# LED_CONTROLLER.net
KiCad netlist of a schematic drawn in Altium Designer
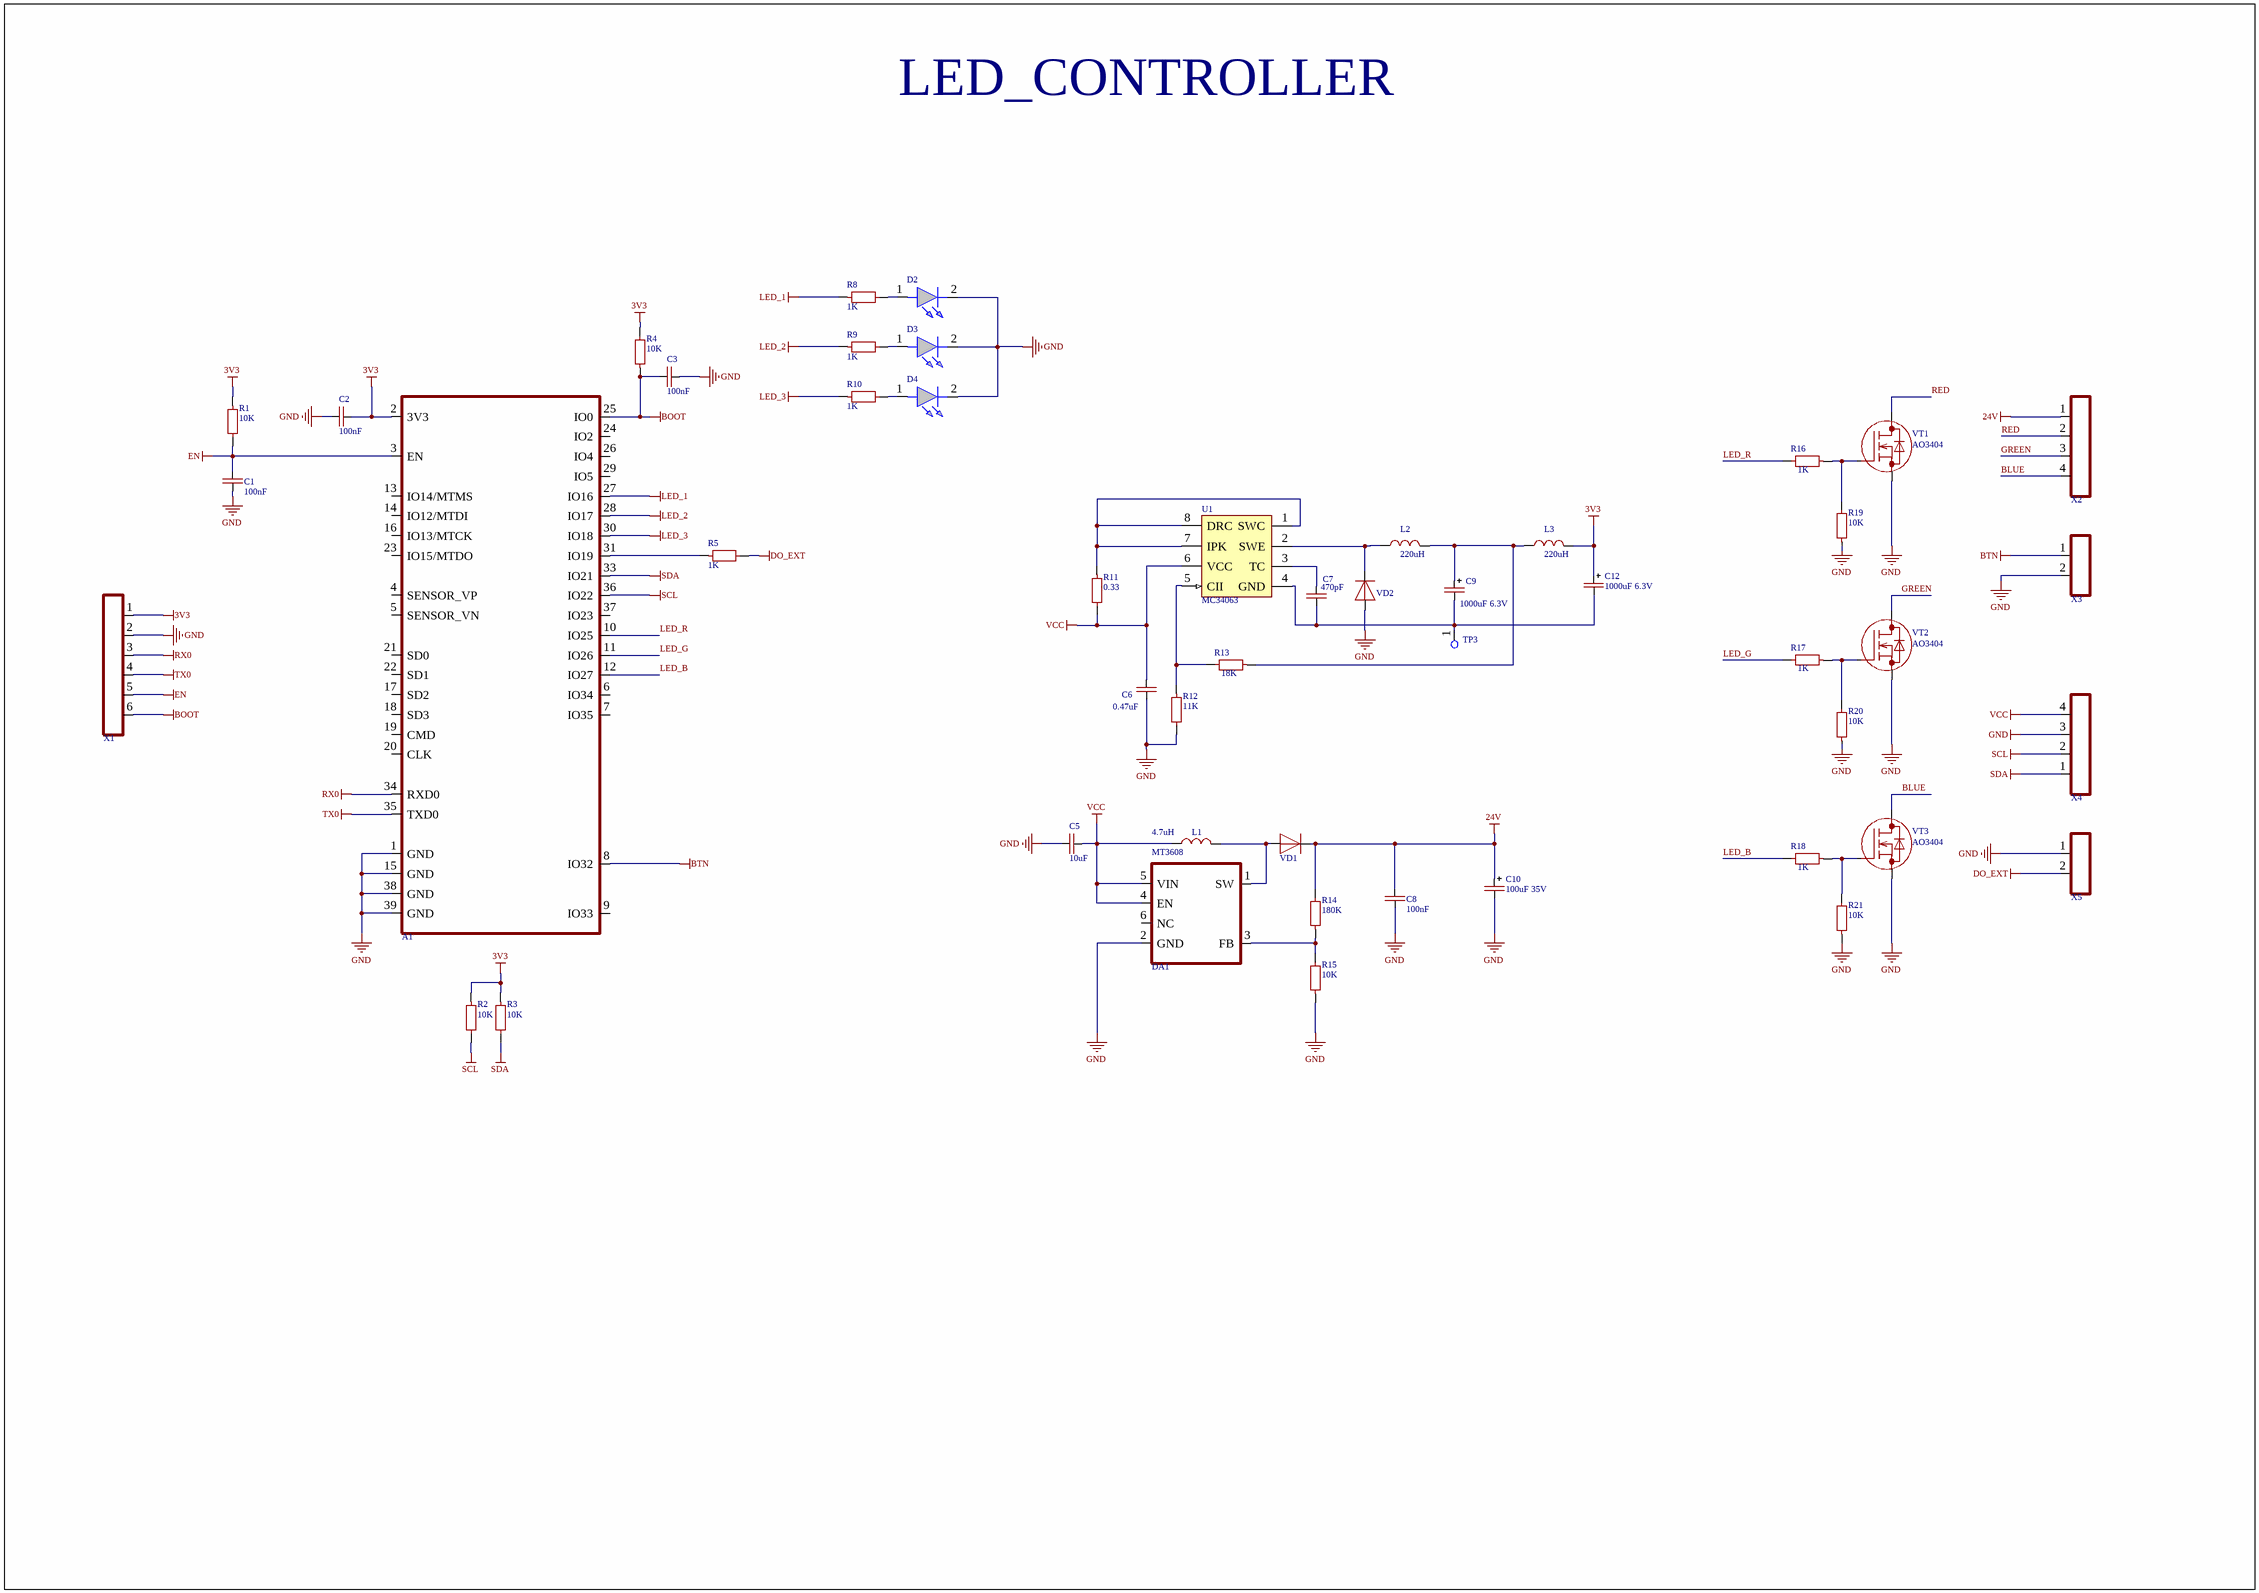
[diagram p0: LED_CONTROLLER.SchDoc]

(export (version "E")
  (design (tool "Eeschema 10.0.6"))
  (components
    (comp (ref "A1")
      (value "MOD-ESP32-WROOM-32E")
      (footprint "MOD-ESP32-WROOM-32E")
      (libsource (lib "MOD-ESP32-WROOM-32E") (part "MOD-ESP32-WROOM-32E"))
    )
    (comp (ref "C1")
      (value "100nF")
      (footprint "CAP-0805")
      (libsource (lib "PASSIVE_COMPONENTS") (part "CAP-NON-POLAR"))
    )
    (comp (ref "C2")
      (value "100nF")
      (footprint "CAP-0805")
      (libsource (lib "PASSIVE_COMPONENTS") (part "CAP-NON-POLAR"))
    )
    (comp (ref "C3")
      (value "100nF")
      (footprint "CAP-0805")
      (libsource (lib "PASSIVE_COMPONENTS") (part "CAP-NON-POLAR"))
    )
    (comp (ref "C5")
      (value "10uF")
      (footprint "CAP-1206")
      (libsource (lib "PASSIVE_COMPONENTS") (part "CAP-NON-POLAR"))
    )
    (comp (ref "C6")
      (value "0.47uF")
      (footprint "CAP-0805")
      (libsource (lib "PASSIVE_COMPONENTS") (part "CAP-NON-POLAR"))
    )
    (comp (ref "C7")
      (value "470pF")
      (footprint "CAP-0805")
      (libsource (lib "PASSIVE_COMPONENTS") (part "CAP-NON-POLAR"))
    )
    (comp (ref "C8")
      (value "100nF")
      (footprint "CAP-0805")
      (libsource (lib "PASSIVE_COMPONENTS") (part "CAP-NON-POLAR"))
    )
    (comp (ref "C9")
      (value "1000uF 6.3V")
      (footprint "CAPPOL_SMD_SIZE_E")
      (libsource (lib "PAS_COMPONENTS") (part "CAP-POLAR"))
    )
    (comp (ref "C10")
      (value "100uF 35V")
      (footprint "CAPPOL_SMD_SIZE_E")
      (libsource (lib "PAS_COMPONENTS") (part "CAP-POLAR"))
    )
    (comp (ref "C12")
      (value "1000uF 6.3V")
      (footprint "CAPPOL_SMD_SIZE_E")
      (libsource (lib "PAS_COMPONENTS") (part "CAP-POLAR"))
    )
    (comp (ref "D2")
      (value "151031YS06000")
      (footprint "LED_BLUE")
      (description "WURTH ELEKTRONIK - 151031YS06000 - LED, Yellow, Through Hole, T-1 (3mm), 30 mA, 2 V, 590 nm")
      (fields (field (name "MOUSER PART NUMBER") "710-151031YS06000"))
      (libsource (lib "Optic-LED") (part "LED"))
    )
    (comp (ref "D3")
      (value "151031YS06000")
      (footprint "LED_BLUE")
      (description "WURTH ELEKTRONIK - 151031YS06000 - LED, Yellow, Through Hole, T-1 (3mm), 30 mA, 2 V, 590 nm")
      (fields (field (name "MOUSER PART NUMBER") "710-151031YS06000"))
      (libsource (lib "Optic-LED") (part "LED"))
    )
    (comp (ref "D4")
      (value "151031YS06000")
      (footprint "LED_BLUE")
      (description "WURTH ELEKTRONIK - 151031YS06000 - LED, Yellow, Through Hole, T-1 (3mm), 30 mA, 2 V, 590 nm")
      (fields (field (name "MOUSER PART NUMBER") "710-151031YS06000"))
      (libsource (lib "Optic-LED") (part "LED"))
    )
    (comp (ref "DA1") (value "MT3608") (footprint "SOT23-6") (libsource (lib "MT3608") (part "MT3608")))
    (comp (ref "L1")
      (value "4.7uH")
      (footprint "IND-7850")
      (libsource (lib "PAS_COMPONENTS") (part "IND-CONST"))
    )
    (comp (ref "L2")
      (value "220uH")
      (footprint "IND-7850")
      (libsource (lib "PAS_COMPONENTS") (part "IND-CONST"))
    )
    (comp (ref "L3")
      (value "220uH")
      (footprint "IND-7850")
      (libsource (lib "PAS_COMPONENTS") (part "IND-CONST"))
    )
    (comp (ref "R1")
      (value "10K")
      (footprint "RES-0805")
      (libsource (lib "PAS_COMPONENTS") (part "RES-CONST"))
    )
    (comp (ref "R2")
      (value "10K")
      (footprint "RES-0805")
      (libsource (lib "PAS_COMPONENTS") (part "RES-CONST"))
    )
    (comp (ref "R3")
      (value "10K")
      (footprint "RES-0805")
      (libsource (lib "PAS_COMPONENTS") (part "RES-CONST"))
    )
    (comp (ref "R4")
      (value "10K")
      (footprint "RES-0805")
      (libsource (lib "PAS_COMPONENTS") (part "RES-CONST"))
    )
    (comp (ref "R5")
      (value "1K")
      (footprint "RES-0805")
      (libsource (lib "PAS_COMPONENTS") (part "RES-CONST"))
    )
    (comp (ref "R8")
      (value "1K")
      (footprint "RES-0805")
      (libsource (lib "PAS_COMPONENTS") (part "RES-CONST"))
    )
    (comp (ref "R9")
      (value "1K")
      (footprint "RES-0805")
      (libsource (lib "PAS_COMPONENTS") (part "RES-CONST"))
    )
    (comp (ref "R10")
      (value "1K")
      (footprint "RES-0805")
      (libsource (lib "PAS_COMPONENTS") (part "RES-CONST"))
    )
    (comp (ref "R11")
      (value "0.33")
      (footprint "RES-2512")
      (libsource (lib "PAS_COMPONENTS") (part "RES-CONST"))
    )
    (comp (ref "R12")
      (value "11K")
      (footprint "RES-0805")
      (libsource (lib "PAS_COMPONENTS") (part "RES-CONST"))
    )
    (comp (ref "R13")
      (value "18K")
      (footprint "RES-0805")
      (libsource (lib "PAS_COMPONENTS") (part "RES-CONST"))
    )
    (comp (ref "R14")
      (value "180K")
      (footprint "RES-0805")
      (libsource (lib "PAS_COMPONENTS") (part "RES-CONST"))
    )
    (comp (ref "R15")
      (value "10K")
      (footprint "RES-0805")
      (libsource (lib "PAS_COMPONENTS") (part "RES-CONST"))
    )
    (comp (ref "R16")
      (value "1K")
      (footprint "RES-0805")
      (libsource (lib "PAS_COMPONENTS") (part "RES-CONST"))
    )
    (comp (ref "R17")
      (value "1K")
      (footprint "RES-0805")
      (libsource (lib "PAS_COMPONENTS") (part "RES-CONST"))
    )
    (comp (ref "R18")
      (value "1K")
      (footprint "RES-0805")
      (libsource (lib "PAS_COMPONENTS") (part "RES-CONST"))
    )
    (comp (ref "R19")
      (value "10K")
      (footprint "RES-0805")
      (libsource (lib "PAS_COMPONENTS") (part "RES-CONST"))
    )
    (comp (ref "R20")
      (value "10K")
      (footprint "RES-0805")
      (libsource (lib "PAS_COMPONENTS") (part "RES-CONST"))
    )
    (comp (ref "R21")
      (value "10K")
      (footprint "RES-0805")
      (libsource (lib "PAS_COMPONENTS") (part "RES-CONST"))
    )
    (comp (ref "TP3")
      (value "Test_Point_PCB")
      (footprint "Pin_Test_Point(Orange)")
      (description "Test_Point")
      (libsource (lib "Connectors") (part "TP_PCB?"))
    )
    (comp (ref "U1")
      (value "MC34063")
      (footprint "SOIC-8_M")
      (libsource (lib "Integrated_Circuts") (part "MC34063"))
    )
    (comp (ref "VD1") (value "DIODE") (footprint "DO-214AC, SMA") (libsource (lib "DO214") (part "DIODE")))
    (comp (ref "VD2") (value "DIODE") (footprint "DO-214AC, SMA") (libsource (lib "DIODES") (part "DIODE")))
    (comp (ref "VT1")
      (value "AO3404")
      (footprint "SOT23-3")
      (libsource (lib "TRANSISTORS") (part "MOSFET-N-GDS"))
    )
    (comp (ref "VT2")
      (value "AO3404")
      (footprint "SOT23-3")
      (libsource (lib "TRANSISTORS") (part "MOSFET-N-GDS"))
    )
    (comp (ref "VT3")
      (value "AO3404")
      (footprint "SOT23-3")
      (libsource (lib "TRANSISTORS") (part "MOSFET-N-GDS"))
    )
    (comp (ref "X1")
      (value "CONN-6-PIN")
      (footprint "CONN-PLS-6-2.00mm")
      (libsource (lib "CONN_PLS") (part "CONN-6-PIN"))
    )
    (comp (ref "X2")
      (value "CONN-4-PIN")
      (footprint "CONN-PLS-4-2.54mm")
      (libsource (lib "XH 4PIN") (part "CONN-4-PIN"))
    )
    (comp (ref "X3") (value "CONN-2-PIN") (footprint "XH2") (libsource (lib "XH 2PIN") (part "CONN-2-PIN")))
    (comp (ref "X4")
      (value "CONN-4-PIN")
      (footprint "CONN-PLS-4-2.54mm")
      (libsource (lib "") (part "CONN-4-PIN_1"))
    )
    (comp (ref "X5") (value "CONN-2-PIN") (footprint "XH2") (libsource (lib "XH 2PIN") (part "CONN-2-PIN")))
  )
  (nets
    (net (code "1") (name "/BLUE") (class "Default")
      (node (ref "VT3") (pin "3") (pinfunction "D_3") (pintype "passive"))
      (node (ref "X2") (pin "4") (pinfunction "4_4") (pintype "passive"))
    )
    (net (code "2") (name "/GREEN") (class "Default")
      (node (ref "VT2") (pin "3") (pinfunction "D_3") (pintype "passive"))
      (node (ref "X2") (pin "3") (pinfunction "3_3") (pintype "passive"))
    )
    (net (code "3") (name "/LED_B") (class "Default")
      (node (ref "A1") (pin "12") (pinfunction "IO27_12") (pintype "passive"))
      (node (ref "R18") (pin "2") (pinfunction "2_2") (pintype "passive"))
    )
    (net (code "4") (name "/LED_G") (class "Default")
      (node (ref "A1") (pin "11") (pinfunction "IO26_11") (pintype "passive"))
      (node (ref "R17") (pin "2") (pinfunction "2_2") (pintype "passive"))
    )
    (net (code "5") (name "/LED_R") (class "Default")
      (node (ref "A1") (pin "10") (pinfunction "IO25_10") (pintype "passive"))
      (node (ref "R16") (pin "2") (pinfunction "2_2") (pintype "passive"))
    )
    (net (code "6") (name "/RED") (class "Default")
      (node (ref "VT1") (pin "3") (pinfunction "D_3") (pintype "passive"))
      (node (ref "X2") (pin "2") (pinfunction "2_2") (pintype "passive"))
    )
    (net (code "7") (name "3V3") (class "Default")
      (node (ref "A1") (pin "2") (pinfunction "3V3_2") (pintype "passive"))
      (node (ref "C12") (pin "1") (pinfunction "+_1") (pintype "passive"))
      (node (ref "C2") (pin "1") (pinfunction "1_1") (pintype "passive"))
      (node (ref "L3") (pin "2") (pinfunction "2_2") (pintype "passive"))
      (node (ref "R1") (pin "1") (pinfunction "1_1") (pintype "passive"))
      (node (ref "R2") (pin "1") (pinfunction "1_1") (pintype "passive"))
      (node (ref "R3") (pin "1") (pinfunction "1_1") (pintype "passive"))
      (node (ref "R4") (pin "2") (pinfunction "2_2") (pintype "passive"))
      (node (ref "X1") (pin "1") (pinfunction "1_1") (pintype "passive"))
    )
    (net (code "8") (name "24V") (class "Default")
      (node (ref "C10") (pin "1") (pinfunction "+_1") (pintype "passive"))
      (node (ref "C8") (pin "1") (pinfunction "1_1") (pintype "passive"))
      (node (ref "R14") (pin "2") (pinfunction "2_2") (pintype "passive"))
      (node (ref "VD1") (pin "1") (pinfunction "C_1") (pintype "passive"))
      (node (ref "X2") (pin "1") (pinfunction "1_1") (pintype "passive"))
    )
    (net (code "9") (name "BOOT") (class "Default")
      (node (ref "A1") (pin "25") (pinfunction "IO0_25") (pintype "passive"))
      (node (ref "C3") (pin "2") (pinfunction "2_2") (pintype "passive"))
      (node (ref "R4") (pin "1") (pinfunction "1_1") (pintype "passive"))
      (node (ref "X1") (pin "6") (pinfunction "6_6") (pintype "passive"))
    )
    (net (code "10") (name "BTN") (class "Default")
      (node (ref "A1") (pin "8") (pinfunction "IO32_8") (pintype "passive"))
      (node (ref "X3") (pin "1") (pinfunction "1_1") (pintype "passive"))
    )
    (net (code "11") (name "DO_EXT") (class "Default")
      (node (ref "R5") (pin "2") (pinfunction "2_2") (pintype "passive"))
      (node (ref "X5") (pin "2") (pinfunction "2_2") (pintype "passive"))
    )
    (net (code "12") (name "EN") (class "Default")
      (node (ref "A1") (pin "3") (pinfunction "EN_3") (pintype "passive"))
      (node (ref "C1") (pin "1") (pinfunction "1_1") (pintype "passive"))
      (node (ref "R1") (pin "2") (pinfunction "2_2") (pintype "passive"))
      (node (ref "X1") (pin "5") (pinfunction "5_5") (pintype "passive"))
    )
    (net (code "13") (name "GND") (class "Default")
      (node (ref "A1") (pin "1") (pinfunction "GND_1") (pintype "passive"))
      (node (ref "A1") (pin "15") (pinfunction "GND_15") (pintype "passive"))
      (node (ref "A1") (pin "38") (pinfunction "GND_38") (pintype "passive"))
      (node (ref "A1") (pin "39") (pinfunction "GND_39") (pintype "passive"))
      (node (ref "C1") (pin "2") (pinfunction "2_2") (pintype "passive"))
      (node (ref "C10") (pin "2") (pinfunction "-_2") (pintype "passive"))
      (node (ref "C2") (pin "2") (pinfunction "2_2") (pintype "passive"))
      (node (ref "C3") (pin "1") (pinfunction "1_1") (pintype "passive"))
      (node (ref "C5") (pin "2") (pinfunction "2_2") (pintype "passive"))
      (node (ref "C6") (pin "2") (pinfunction "2_2") (pintype "passive"))
      (node (ref "C8") (pin "2") (pinfunction "2_2") (pintype "passive"))
      (node (ref "D2") (pin "2") (pinfunction "K_2") (pintype "passive"))
      (node (ref "D3") (pin "2") (pinfunction "K_2") (pintype "passive"))
      (node (ref "D4") (pin "2") (pinfunction "K_2") (pintype "passive"))
      (node (ref "DA1") (pin "2") (pinfunction "GND_2") (pintype "passive"))
      (node (ref "R12") (pin "2") (pinfunction "2_2") (pintype "passive"))
      (node (ref "R15") (pin "1") (pinfunction "1_1") (pintype "passive"))
      (node (ref "R19") (pin "1") (pinfunction "1_1") (pintype "passive"))
      (node (ref "R20") (pin "1") (pinfunction "1_1") (pintype "passive"))
      (node (ref "R21") (pin "1") (pinfunction "1_1") (pintype "passive"))
      (node (ref "VD2") (pin "2") (pinfunction "A_2") (pintype "passive"))
      (node (ref "VT1") (pin "2") (pinfunction "S_2") (pintype "passive"))
      (node (ref "VT2") (pin "2") (pinfunction "S_2") (pintype "passive"))
      (node (ref "VT3") (pin "2") (pinfunction "S_2") (pintype "passive"))
      (node (ref "X1") (pin "2") (pinfunction "2_2") (pintype "passive"))
      (node (ref "X3") (pin "2") (pinfunction "2_2") (pintype "passive"))
      (node (ref "X4") (pin "3") (pinfunction "3_3") (pintype "passive"))
      (node (ref "X5") (pin "1") (pinfunction "1_1") (pintype "passive"))
    )
    (net (code "14") (name "LED_1") (class "Default")
      (node (ref "A1") (pin "27") (pinfunction "IO16_27") (pintype "passive"))
      (node (ref "R8") (pin "1") (pinfunction "1_1") (pintype "passive"))
    )
    (net (code "15") (name "LED_2") (class "Default")
      (node (ref "A1") (pin "28") (pinfunction "IO17_28") (pintype "passive"))
      (node (ref "R9") (pin "1") (pinfunction "1_1") (pintype "passive"))
    )
    (net (code "16") (name "LED_3") (class "Default")
      (node (ref "A1") (pin "30") (pinfunction "IO18_30") (pintype "passive"))
      (node (ref "R10") (pin "1") (pinfunction "1_1") (pintype "passive"))
    )
    (net (code "17") (name "Net-(A1-IO19)") (class "Default")
      (node (ref "A1") (pin "31") (pinfunction "IO19_31") (pintype "passive"))
      (node (ref "R5") (pin "1") (pinfunction "1_1") (pintype "passive"))
    )
    (net (code "18") (name "Net-(C9-+)") (class "Default")
      (node (ref "C9") (pin "1") (pinfunction "+_1") (pintype "passive"))
      (node (ref "L2") (pin "2") (pinfunction "2_2") (pintype "passive"))
      (node (ref "L3") (pin "1") (pinfunction "1_1") (pintype "passive"))
      (node (ref "R13") (pin "1") (pinfunction "1_1") (pintype "passive"))
    )
    (net (code "19") (name "Net-(C12--)") (class "Default")
      (node (ref "C12") (pin "2") (pinfunction "-_2") (pintype "passive"))
      (node (ref "C7") (pin "2") (pinfunction "2_2") (pintype "passive"))
      (node (ref "C9") (pin "2") (pinfunction "-_2") (pintype "passive"))
      (node (ref "TP3") (pin "1") (pinfunction "G9_1") (pintype "passive"))
      (node (ref "U1") (pin "4") (pinfunction "GND_4") (pintype "power_in"))
    )
    (net (code "20") (name "Net-(D2-A)") (class "Default")
      (node (ref "D2") (pin "1") (pinfunction "A_1") (pintype "passive"))
      (node (ref "R8") (pin "2") (pinfunction "2_2") (pintype "passive"))
    )
    (net (code "21") (name "Net-(D3-A)") (class "Default")
      (node (ref "D3") (pin "1") (pinfunction "A_1") (pintype "passive"))
      (node (ref "R9") (pin "2") (pinfunction "2_2") (pintype "passive"))
    )
    (net (code "22") (name "Net-(D4-A)") (class "Default")
      (node (ref "D4") (pin "1") (pinfunction "A_1") (pintype "passive"))
      (node (ref "R10") (pin "2") (pinfunction "2_2") (pintype "passive"))
    )
    (net (code "23") (name "Net-(DA1-FB)") (class "Default")
      (node (ref "DA1") (pin "3") (pinfunction "FB_3") (pintype "passive"))
      (node (ref "R14") (pin "1") (pinfunction "1_1") (pintype "passive"))
      (node (ref "R15") (pin "2") (pinfunction "2_2") (pintype "passive"))
    )
    (net (code "24") (name "Net-(DA1-SW)") (class "Default")
      (node (ref "DA1") (pin "1") (pinfunction "SW_1") (pintype "passive"))
      (node (ref "L1") (pin "2") (pinfunction "2_2") (pintype "passive"))
      (node (ref "VD1") (pin "2") (pinfunction "A_2") (pintype "passive"))
    )
    (net (code "25") (name "Net-(U1-CII)") (class "Default")
      (node (ref "R12") (pin "1") (pinfunction "1_1") (pintype "passive"))
      (node (ref "R13") (pin "2") (pinfunction "2_2") (pintype "passive"))
      (node (ref "U1") (pin "5") (pinfunction "CII_5") (pintype "input"))
    )
    (net (code "26") (name "Net-(U1-DRC)") (class "Default")
      (node (ref "R11") (pin "1") (pinfunction "1_1") (pintype "passive"))
      (node (ref "U1") (pin "1") (pinfunction "SWC_1") (pintype "open_collector"))
      (node (ref "U1") (pin "7") (pinfunction "IPK_7") (pintype "passive"))
      (node (ref "U1") (pin "8") (pinfunction "DRC_8") (pintype "open_collector"))
    )
    (net (code "27") (name "Net-(U1-SWE)") (class "Default")
      (node (ref "L2") (pin "1") (pinfunction "1_1") (pintype "passive"))
      (node (ref "U1") (pin "2") (pinfunction "SWE_2") (pintype "open_emitter"))
      (node (ref "VD2") (pin "1") (pinfunction "C_1") (pintype "passive"))
    )
    (net (code "28") (name "Net-(U1-TC)") (class "Default")
      (node (ref "C7") (pin "1") (pinfunction "1_1") (pintype "passive"))
      (node (ref "U1") (pin "3") (pinfunction "TC_3") (pintype "passive"))
    )
    (net (code "29") (name "Net-(VT1-G)") (class "Default")
      (node (ref "R16") (pin "1") (pinfunction "1_1") (pintype "passive"))
      (node (ref "R19") (pin "2") (pinfunction "2_2") (pintype "passive"))
      (node (ref "VT1") (pin "1") (pinfunction "G_1") (pintype "passive"))
    )
    (net (code "30") (name "Net-(VT2-G)") (class "Default")
      (node (ref "R17") (pin "1") (pinfunction "1_1") (pintype "passive"))
      (node (ref "R20") (pin "2") (pinfunction "2_2") (pintype "passive"))
      (node (ref "VT2") (pin "1") (pinfunction "G_1") (pintype "passive"))
    )
    (net (code "31") (name "Net-(VT3-G)") (class "Default")
      (node (ref "R18") (pin "1") (pinfunction "1_1") (pintype "passive"))
      (node (ref "R21") (pin "2") (pinfunction "2_2") (pintype "passive"))
      (node (ref "VT3") (pin "1") (pinfunction "G_1") (pintype "passive"))
    )
    (net (code "32") (name "RX0") (class "Default")
      (node (ref "A1") (pin "34") (pinfunction "RXD0_34") (pintype "passive"))
      (node (ref "X1") (pin "3") (pinfunction "3_3") (pintype "passive"))
    )
    (net (code "33") (name "SCL") (class "Default")
      (node (ref "A1") (pin "36") (pinfunction "IO22_36") (pintype "passive"))
      (node (ref "R2") (pin "2") (pinfunction "2_2") (pintype "passive"))
      (node (ref "X4") (pin "2") (pinfunction "2_2") (pintype "passive"))
    )
    (net (code "34") (name "SDA") (class "Default")
      (node (ref "A1") (pin "33") (pinfunction "IO21_33") (pintype "passive"))
      (node (ref "R3") (pin "2") (pinfunction "2_2") (pintype "passive"))
      (node (ref "X4") (pin "1") (pinfunction "1_1") (pintype "passive"))
    )
    (net (code "35") (name "TX0") (class "Default")
      (node (ref "A1") (pin "35") (pinfunction "TXD0_35") (pintype "passive"))
      (node (ref "X1") (pin "4") (pinfunction "4_4") (pintype "passive"))
    )
    (net (code "36") (name "VCC") (class "Default")
      (node (ref "C5") (pin "1") (pinfunction "1_1") (pintype "passive"))
      (node (ref "C6") (pin "1") (pinfunction "1_1") (pintype "passive"))
      (node (ref "DA1") (pin "4") (pinfunction "EN_4") (pintype "passive"))
      (node (ref "DA1") (pin "5") (pinfunction "VIN_5") (pintype "passive"))
      (node (ref "L1") (pin "1") (pinfunction "1_1") (pintype "passive"))
      (node (ref "R11") (pin "2") (pinfunction "2_2") (pintype "passive"))
      (node (ref "U1") (pin "6") (pinfunction "VCC_6") (pintype "power_in"))
      (node (ref "X4") (pin "4") (pinfunction "4_4") (pintype "passive"))
    )
    (net (code "37") (name "unconnected-(A1-CLK-Pad20)") (class "Default")
      (node (ref "A1") (pin "20") (pinfunction "CLK_20") (pintype "passive"))
    )
    (net (code "38") (name "unconnected-(A1-CMD-Pad19)") (class "Default")
      (node (ref "A1") (pin "19") (pinfunction "CMD_19") (pintype "passive"))
    )
    (net (code "39") (name "unconnected-(A1-IO2-Pad24)") (class "Default")
      (node (ref "A1") (pin "24") (pinfunction "IO2_24") (pintype "passive"))
    )
    (net (code "40") (name "unconnected-(A1-IO4-Pad26)") (class "Default")
      (node (ref "A1") (pin "26") (pinfunction "IO4_26") (pintype "passive"))
    )
    (net (code "41") (name "unconnected-(A1-IO5-Pad29)") (class "Default")
      (node (ref "A1") (pin "29") (pinfunction "IO5_29") (pintype "passive"))
    )
    (net (code "42") (name "unconnected-(A1-IO12{slash}MTDI-Pad14)") (class "Default")
      (node (ref "A1") (pin "14") (pinfunction "IO12/MTDI_14") (pintype "passive"))
    )
    (net (code "43") (name "unconnected-(A1-IO13{slash}MTCK-Pad16)") (class "Default")
      (node (ref "A1") (pin "16") (pinfunction "IO13/MTCK_16") (pintype "passive"))
    )
    (net (code "44") (name "unconnected-(A1-IO14{slash}MTMS-Pad13)") (class "Default")
      (node (ref "A1") (pin "13") (pinfunction "IO14/MTMS_13") (pintype "passive"))
    )
    (net (code "45") (name "unconnected-(A1-IO15{slash}MTDO-Pad23)") (class "Default")
      (node (ref "A1") (pin "23") (pinfunction "IO15/MTDO_23") (pintype "passive"))
    )
    (net (code "46") (name "unconnected-(A1-IO23-Pad37)") (class "Default")
      (node (ref "A1") (pin "37") (pinfunction "IO23_37") (pintype "passive"))
    )
    (net (code "47") (name "unconnected-(A1-IO33-Pad9)") (class "Default")
      (node (ref "A1") (pin "9") (pinfunction "IO33_9") (pintype "passive"))
    )
    (net (code "48") (name "unconnected-(A1-IO34-Pad6)") (class "Default")
      (node (ref "A1") (pin "6") (pinfunction "IO34_6") (pintype "passive"))
    )
    (net (code "49") (name "unconnected-(A1-IO35-Pad7)") (class "Default")
      (node (ref "A1") (pin "7") (pinfunction "IO35_7") (pintype "passive"))
    )
    (net (code "50") (name "unconnected-(A1-SD0-Pad21)") (class "Default")
      (node (ref "A1") (pin "21") (pinfunction "SD0_21") (pintype "passive"))
    )
    (net (code "51") (name "unconnected-(A1-SD1-Pad22)") (class "Default")
      (node (ref "A1") (pin "22") (pinfunction "SD1_22") (pintype "passive"))
    )
    (net (code "52") (name "unconnected-(A1-SD2-Pad17)") (class "Default")
      (node (ref "A1") (pin "17") (pinfunction "SD2_17") (pintype "passive"))
    )
    (net (code "53") (name "unconnected-(A1-SD3-Pad18)") (class "Default")
      (node (ref "A1") (pin "18") (pinfunction "SD3_18") (pintype "passive"))
    )
    (net (code "54") (name "unconnected-(A1-SENSOR_VN-Pad5)") (class "Default")
      (node (ref "A1") (pin "5") (pinfunction "SENSOR_VN_5") (pintype "passive"))
    )
    (net (code "55") (name "unconnected-(A1-SENSOR_VP-Pad4)") (class "Default")
      (node (ref "A1") (pin "4") (pinfunction "SENSOR_VP_4") (pintype "passive"))
    )
    (net (code "56") (name "unconnected-(DA1-NC-Pad6)") (class "Default")
      (node (ref "DA1") (pin "6") (pinfunction "NC_6") (pintype "passive"))
    )
  )
)
